# my_flow_pcb.net
KiCad netlist of a schematic drawn in EAGLE
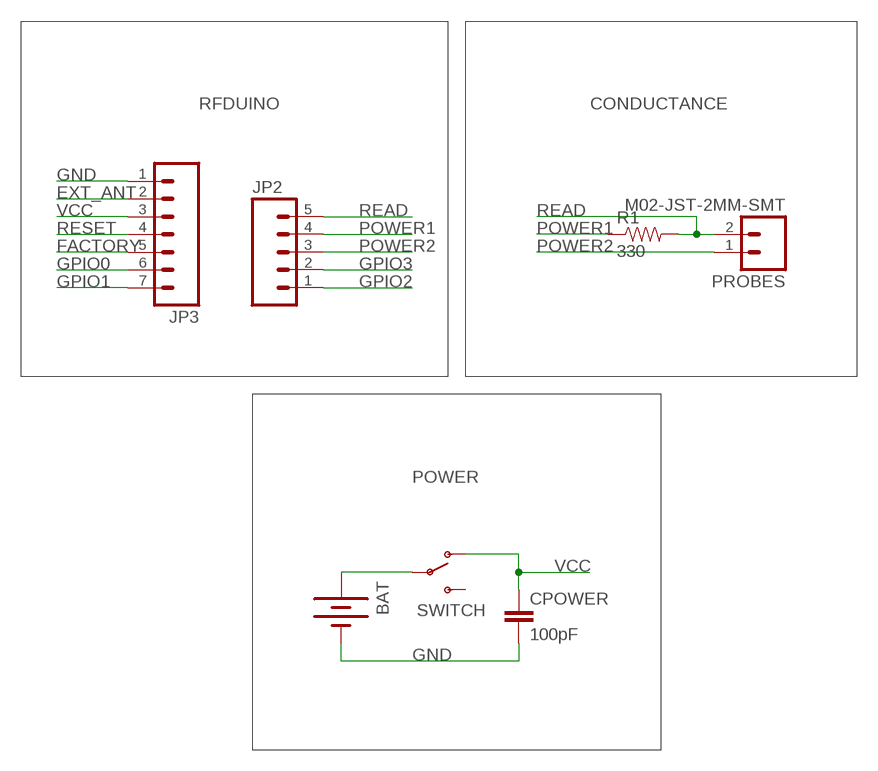
[diagram p0: schematic, sheet 1]

(export (version "E")
  (design (tool "Eeschema 10.0.6"))
  (components
    (comp (ref "BAT")
      (value "BATTERY12MM")
      (footprint "eagle-import:BATTCON_12MM")
      (libsource (lib "eagle-import") (part "BATTERY12MM"))
    )
    (comp (ref "CPOWER")
      (value "100pF")
      (footprint "eagle-import:0805")
      (libsource (lib "eagle-import") (part "CAP0805"))
    )
    (comp (ref "JP2")
      (value "M05PTH")
      (footprint "eagle-import:1X05")
      (libsource (lib "eagle-import") (part "M05PTH"))
    )
    (comp (ref "JP3")
      (value "M07")
      (footprint "eagle-import:1X07")
      (libsource (lib "eagle-import") (part "M07"))
    )
    (comp (ref "PROBES")
      (value "M02-JST-2MM-SMT")
      (footprint "eagle-import:JST-2-SMD")
      (libsource (lib "eagle-import") (part "M02-JST-2MM-SMT"))
    )
    (comp (ref "R1")
      (value "330")
      (footprint "eagle-import:0805")
      (libsource (lib "eagle-import") (part "RESISTOR0805-RES"))
    )
    (comp (ref "SWITCH")
      (value "SWITCH-SPDT-SMD-A")
      (footprint "eagle-import:SWITCH-SPST-SMD-A")
      (libsource (lib "eagle-import") (part "SWITCH-SPDT-SMD-A"))
    )
  )
  (nets
    (net (code "1") (name "/EXT_ANT") (class "Default")
      (node (ref "JP3") (pin "2") (pinfunction "2_2") (pintype "passive"))
    )
    (net (code "2") (name "/FACTORY") (class "Default")
      (node (ref "JP3") (pin "5") (pinfunction "5_5") (pintype "passive"))
    )
    (net (code "3") (name "/GND") (class "Default")
      (node (ref "BAT") (pin "GND") (pinfunction "-_GND") (pintype "power_in"))
      (node (ref "CPOWER") (pin "2") (pinfunction "2_2") (pintype "passive"))
      (node (ref "JP3") (pin "1") (pinfunction "1_1") (pintype "passive"))
    )
    (net (code "4") (name "/GPIO0") (class "Default")
      (node (ref "JP3") (pin "6") (pinfunction "6_6") (pintype "passive"))
    )
    (net (code "5") (name "/GPIO1") (class "Default")
      (node (ref "JP3") (pin "7") (pinfunction "7_7") (pintype "passive"))
    )
    (net (code "6") (name "/GPIO2") (class "Default")
      (node (ref "JP2") (pin "1") (pinfunction "1_1") (pintype "passive"))
    )
    (net (code "7") (name "/GPIO3") (class "Default")
      (node (ref "JP2") (pin "2") (pinfunction "2_2") (pintype "passive"))
    )
    (net (code "8") (name "/POWER1") (class "Default")
      (node (ref "JP2") (pin "4") (pinfunction "4_4") (pintype "passive"))
      (node (ref "R1") (pin "1") (pinfunction "1_1") (pintype "passive"))
    )
    (net (code "9") (name "/POWER2") (class "Default")
      (node (ref "JP2") (pin "3") (pinfunction "3_3") (pintype "passive"))
      (node (ref "PROBES") (pin "1") (pinfunction "2_1") (pintype "passive"))
    )
    (net (code "10") (name "/READ") (class "Default")
      (node (ref "JP2") (pin "5") (pinfunction "5_5") (pintype "passive"))
      (node (ref "PROBES") (pin "2") (pinfunction "1_2") (pintype "passive"))
      (node (ref "R1") (pin "2") (pinfunction "2_2") (pintype "passive"))
    )
    (net (code "11") (name "/RESET") (class "Default")
      (node (ref "JP3") (pin "4") (pinfunction "4_4") (pintype "passive"))
    )
    (net (code "12") (name "/VCC") (class "Default")
      (node (ref "CPOWER") (pin "1") (pinfunction "1_1") (pintype "passive"))
      (node (ref "JP3") (pin "3") (pinfunction "3_3") (pintype "passive"))
      (node (ref "SWITCH") (pin "1") (pinfunction "O_1") (pintype "passive"))
    )
    (net (code "13") (name "Net-(BAT-+)") (class "Default")
      (node (ref "BAT") (pin "PWR@1") (pinfunction "+_PWR@1") (pintype "power_in"))
      (node (ref "SWITCH") (pin "2") (pinfunction "P_2") (pintype "passive"))
    )
    (net (code "14") (name "unconnected-(SWITCH-S-Pad3)") (class "Default")
      (node (ref "SWITCH") (pin "3") (pinfunction "S_3") (pintype "passive"))
    )
  )
)
